# led_serial_strip_small_v1_1.net
KiCad netlist of a schematic drawn in EAGLE
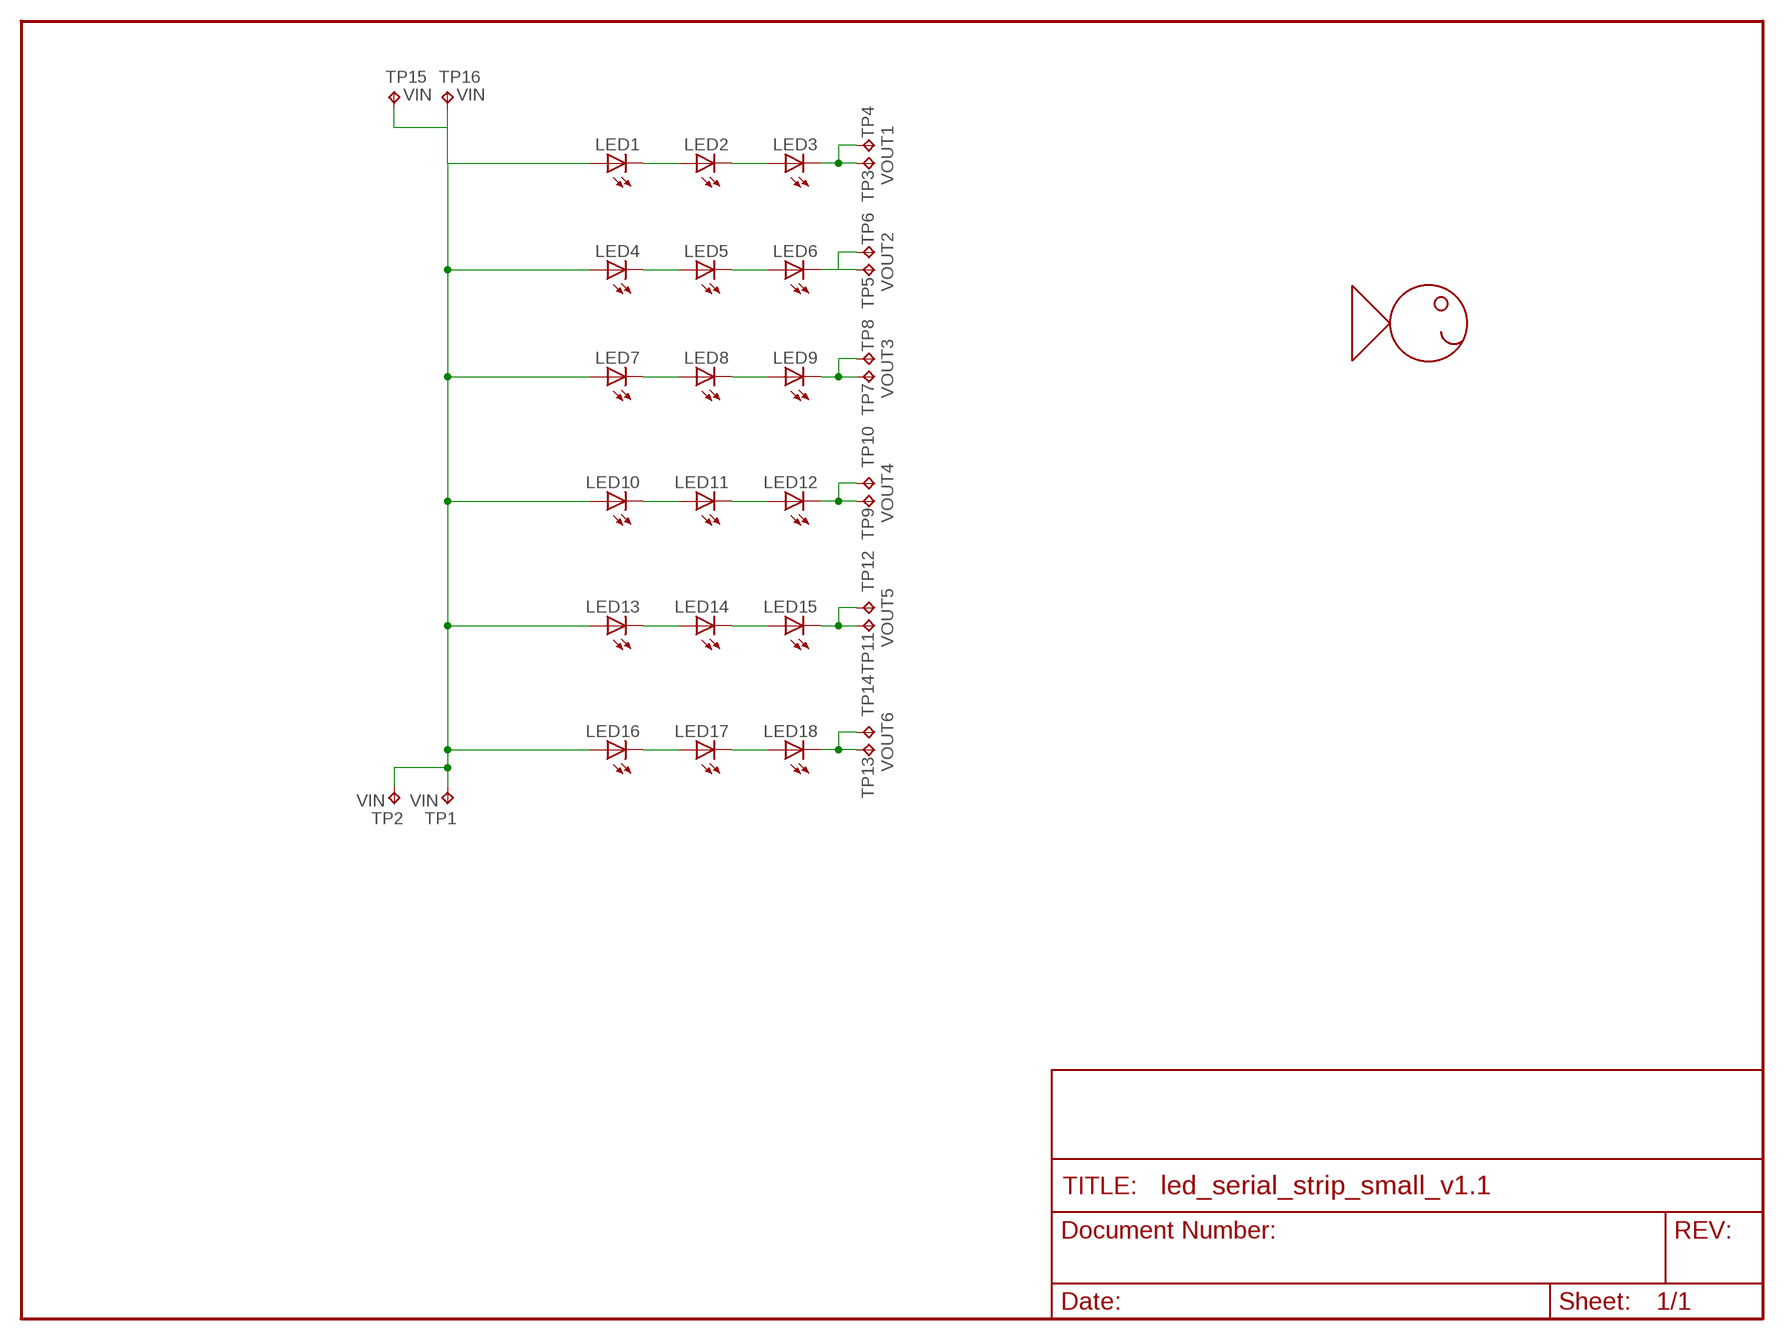
[diagram p0: schematic, sheet 1]

(export (version "E")
  (design (tool "Eeschema 10.0.6"))
  (components
    (comp (ref "LED1")
      (value "LED0805")
      (footprint "eagle-import:LED_0805")
      (libsource (lib "eagle-import") (part "LED0805"))
    )
    (comp (ref "LED2")
      (value "LED0805")
      (footprint "eagle-import:LED_0805")
      (libsource (lib "eagle-import") (part "LED0805"))
    )
    (comp (ref "LED3")
      (value "LED0805")
      (footprint "eagle-import:LED_0805")
      (libsource (lib "eagle-import") (part "LED0805"))
    )
    (comp (ref "LED4")
      (value "LED0805")
      (footprint "eagle-import:LED_0805")
      (libsource (lib "eagle-import") (part "LED0805"))
    )
    (comp (ref "LED5")
      (value "LED0805")
      (footprint "eagle-import:LED_0805")
      (libsource (lib "eagle-import") (part "LED0805"))
    )
    (comp (ref "LED6")
      (value "LED0805")
      (footprint "eagle-import:LED_0805")
      (libsource (lib "eagle-import") (part "LED0805"))
    )
    (comp (ref "LED7")
      (value "LED0805")
      (footprint "eagle-import:LED_0805")
      (libsource (lib "eagle-import") (part "LED0805"))
    )
    (comp (ref "LED8")
      (value "LED0805")
      (footprint "eagle-import:LED_0805")
      (libsource (lib "eagle-import") (part "LED0805"))
    )
    (comp (ref "LED9")
      (value "LED0805")
      (footprint "eagle-import:LED_0805")
      (libsource (lib "eagle-import") (part "LED0805"))
    )
    (comp (ref "LED10")
      (value "LED0805")
      (footprint "eagle-import:LED_0805")
      (libsource (lib "eagle-import") (part "LED0805"))
    )
    (comp (ref "LED11")
      (value "LED0805")
      (footprint "eagle-import:LED_0805")
      (libsource (lib "eagle-import") (part "LED0805"))
    )
    (comp (ref "LED12")
      (value "LED0805")
      (footprint "eagle-import:LED_0805")
      (libsource (lib "eagle-import") (part "LED0805"))
    )
    (comp (ref "LED13")
      (value "LED0805")
      (footprint "eagle-import:LED_0805")
      (libsource (lib "eagle-import") (part "LED0805"))
    )
    (comp (ref "LED14")
      (value "LED0805")
      (footprint "eagle-import:LED_0805")
      (libsource (lib "eagle-import") (part "LED0805"))
    )
    (comp (ref "LED15")
      (value "LED0805")
      (footprint "eagle-import:LED_0805")
      (libsource (lib "eagle-import") (part "LED0805"))
    )
    (comp (ref "LED16")
      (value "LED0805")
      (footprint "eagle-import:LED_0805")
      (libsource (lib "eagle-import") (part "LED0805"))
    )
    (comp (ref "LED17")
      (value "LED0805")
      (footprint "eagle-import:LED_0805")
      (libsource (lib "eagle-import") (part "LED0805"))
    )
    (comp (ref "LED18")
      (value "LED0805")
      (footprint "eagle-import:LED_0805")
      (libsource (lib "eagle-import") (part "LED0805"))
    )
    (comp (ref "TP1")
      (value "VIN")
      (footprint "eagle-import:P1-20")
      (libsource (lib "eagle-import") (part "TEST_POINTPAD1-20"))
    )
    (comp (ref "TP2")
      (value "VIN")
      (footprint "eagle-import:P1-20")
      (libsource (lib "eagle-import") (part "TEST_POINTPAD1-20"))
    )
    (comp (ref "TP3")
      (value "VOUT1")
      (footprint "eagle-import:P1-20")
      (libsource (lib "eagle-import") (part "TEST_POINTPAD1-20"))
    )
    (comp (ref "TP4")
      (value "VOUT1")
      (footprint "eagle-import:P1-20")
      (libsource (lib "eagle-import") (part "TEST_POINTPAD1-20"))
    )
    (comp (ref "TP5")
      (value "VOUT2")
      (footprint "eagle-import:P1-20")
      (libsource (lib "eagle-import") (part "TEST_POINTPAD1-20"))
    )
    (comp (ref "TP6")
      (value "VOUT2")
      (footprint "eagle-import:P1-20")
      (libsource (lib "eagle-import") (part "TEST_POINTPAD1-20"))
    )
    (comp (ref "TP7")
      (value "VOUT3")
      (footprint "eagle-import:P1-20")
      (libsource (lib "eagle-import") (part "TEST_POINTPAD1-20"))
    )
    (comp (ref "TP8")
      (value "VOUT3")
      (footprint "eagle-import:P1-20")
      (libsource (lib "eagle-import") (part "TEST_POINTPAD1-20"))
    )
    (comp (ref "TP9")
      (value "VOUT4")
      (footprint "eagle-import:P1-20")
      (libsource (lib "eagle-import") (part "TEST_POINTPAD1-20"))
    )
    (comp (ref "TP10")
      (value "VOUT4")
      (footprint "eagle-import:P1-20")
      (libsource (lib "eagle-import") (part "TEST_POINTPAD1-20"))
    )
    (comp (ref "TP11")
      (value "VOUT5")
      (footprint "eagle-import:P1-20")
      (libsource (lib "eagle-import") (part "TEST_POINTPAD1-20"))
    )
    (comp (ref "TP12")
      (value "VOUT5")
      (footprint "eagle-import:P1-20")
      (libsource (lib "eagle-import") (part "TEST_POINTPAD1-20"))
    )
    (comp (ref "TP13")
      (value "VOUT6")
      (footprint "eagle-import:P1-20")
      (libsource (lib "eagle-import") (part "TEST_POINTPAD1-20"))
    )
    (comp (ref "TP14")
      (value "VOUT6")
      (footprint "eagle-import:P1-20")
      (libsource (lib "eagle-import") (part "TEST_POINTPAD1-20"))
    )
    (comp (ref "TP15")
      (value "VIN")
      (footprint "eagle-import:P1-20")
      (libsource (lib "eagle-import") (part "TEST_POINTPAD1-20"))
    )
    (comp (ref "TP16")
      (value "VIN")
      (footprint "eagle-import:P1-20")
      (libsource (lib "eagle-import") (part "TEST_POINTPAD1-20"))
    )
    (comp (ref "U$1")
      (value "FHI_LOGO")
      (footprint "eagle-import:FHI_LOGO")
      (libsource (lib "eagle-import") (part "FHI_LOGO"))
    )
  )
  (nets
    (net (code "1") (name "Net-(LED1-PadA)") (class "Default")
      (node (ref "LED1") (pin "A") (pinfunction "A_A") (pintype "passive"))
      (node (ref "LED10") (pin "A") (pinfunction "A_A") (pintype "passive"))
      (node (ref "LED13") (pin "A") (pinfunction "A_A") (pintype "passive"))
      (node (ref "LED16") (pin "A") (pinfunction "A_A") (pintype "passive"))
      (node (ref "LED4") (pin "A") (pinfunction "A_A") (pintype "passive"))
      (node (ref "LED7") (pin "A") (pinfunction "A_A") (pintype "passive"))
      (node (ref "TP1") (pin "TP") (pinfunction "TP_TP") (pintype "input"))
      (node (ref "TP15") (pin "TP") (pinfunction "TP_TP") (pintype "input"))
      (node (ref "TP16") (pin "TP") (pinfunction "TP_TP") (pintype "input"))
      (node (ref "TP2") (pin "TP") (pinfunction "TP_TP") (pintype "input"))
    )
    (net (code "2") (name "Net-(LED1-PadC)") (class "Default")
      (node (ref "LED1") (pin "C") (pinfunction "C_C") (pintype "passive"))
      (node (ref "LED2") (pin "A") (pinfunction "A_A") (pintype "passive"))
    )
    (net (code "3") (name "Net-(LED2-PadC)") (class "Default")
      (node (ref "LED2") (pin "C") (pinfunction "C_C") (pintype "passive"))
      (node (ref "LED3") (pin "A") (pinfunction "A_A") (pintype "passive"))
    )
    (net (code "4") (name "Net-(LED3-PadC)") (class "Default")
      (node (ref "LED3") (pin "C") (pinfunction "C_C") (pintype "passive"))
      (node (ref "TP3") (pin "TP") (pinfunction "TP_TP") (pintype "input"))
      (node (ref "TP4") (pin "TP") (pinfunction "TP_TP") (pintype "input"))
    )
    (net (code "5") (name "Net-(LED4-PadC)") (class "Default")
      (node (ref "LED4") (pin "C") (pinfunction "C_C") (pintype "passive"))
      (node (ref "LED5") (pin "A") (pinfunction "A_A") (pintype "passive"))
    )
    (net (code "6") (name "Net-(LED5-PadC)") (class "Default")
      (node (ref "LED5") (pin "C") (pinfunction "C_C") (pintype "passive"))
      (node (ref "LED6") (pin "A") (pinfunction "A_A") (pintype "passive"))
    )
    (net (code "7") (name "Net-(LED6-PadC)") (class "Default")
      (node (ref "LED6") (pin "C") (pinfunction "C_C") (pintype "passive"))
      (node (ref "TP5") (pin "TP") (pinfunction "TP_TP") (pintype "input"))
      (node (ref "TP6") (pin "TP") (pinfunction "TP_TP") (pintype "input"))
    )
    (net (code "8") (name "Net-(LED7-PadC)") (class "Default")
      (node (ref "LED7") (pin "C") (pinfunction "C_C") (pintype "passive"))
      (node (ref "LED8") (pin "A") (pinfunction "A_A") (pintype "passive"))
    )
    (net (code "9") (name "Net-(LED8-PadC)") (class "Default")
      (node (ref "LED8") (pin "C") (pinfunction "C_C") (pintype "passive"))
      (node (ref "LED9") (pin "A") (pinfunction "A_A") (pintype "passive"))
    )
    (net (code "10") (name "Net-(LED9-PadC)") (class "Default")
      (node (ref "LED9") (pin "C") (pinfunction "C_C") (pintype "passive"))
      (node (ref "TP7") (pin "TP") (pinfunction "TP_TP") (pintype "input"))
      (node (ref "TP8") (pin "TP") (pinfunction "TP_TP") (pintype "input"))
    )
    (net (code "11") (name "Net-(LED10-PadC)") (class "Default")
      (node (ref "LED10") (pin "C") (pinfunction "C_C") (pintype "passive"))
      (node (ref "LED11") (pin "A") (pinfunction "A_A") (pintype "passive"))
    )
    (net (code "12") (name "Net-(LED11-PadC)") (class "Default")
      (node (ref "LED11") (pin "C") (pinfunction "C_C") (pintype "passive"))
      (node (ref "LED12") (pin "A") (pinfunction "A_A") (pintype "passive"))
    )
    (net (code "13") (name "Net-(LED12-PadC)") (class "Default")
      (node (ref "LED12") (pin "C") (pinfunction "C_C") (pintype "passive"))
      (node (ref "TP10") (pin "TP") (pinfunction "TP_TP") (pintype "input"))
      (node (ref "TP9") (pin "TP") (pinfunction "TP_TP") (pintype "input"))
    )
    (net (code "14") (name "Net-(LED13-PadC)") (class "Default")
      (node (ref "LED13") (pin "C") (pinfunction "C_C") (pintype "passive"))
      (node (ref "LED14") (pin "A") (pinfunction "A_A") (pintype "passive"))
    )
    (net (code "15") (name "Net-(LED14-PadC)") (class "Default")
      (node (ref "LED14") (pin "C") (pinfunction "C_C") (pintype "passive"))
      (node (ref "LED15") (pin "A") (pinfunction "A_A") (pintype "passive"))
    )
    (net (code "16") (name "Net-(LED15-PadC)") (class "Default")
      (node (ref "LED15") (pin "C") (pinfunction "C_C") (pintype "passive"))
      (node (ref "TP11") (pin "TP") (pinfunction "TP_TP") (pintype "input"))
      (node (ref "TP12") (pin "TP") (pinfunction "TP_TP") (pintype "input"))
    )
    (net (code "17") (name "Net-(LED16-PadC)") (class "Default")
      (node (ref "LED16") (pin "C") (pinfunction "C_C") (pintype "passive"))
      (node (ref "LED17") (pin "A") (pinfunction "A_A") (pintype "passive"))
    )
    (net (code "18") (name "Net-(LED17-PadC)") (class "Default")
      (node (ref "LED17") (pin "C") (pinfunction "C_C") (pintype "passive"))
      (node (ref "LED18") (pin "A") (pinfunction "A_A") (pintype "passive"))
    )
    (net (code "19") (name "Net-(LED18-PadC)") (class "Default")
      (node (ref "LED18") (pin "C") (pinfunction "C_C") (pintype "passive"))
      (node (ref "TP13") (pin "TP") (pinfunction "TP_TP") (pintype "input"))
      (node (ref "TP14") (pin "TP") (pinfunction "TP_TP") (pintype "input"))
    )
  )
)
